# Motor_Temp_Measurement.net
KiCad netlist of a schematic drawn in Altium Designer
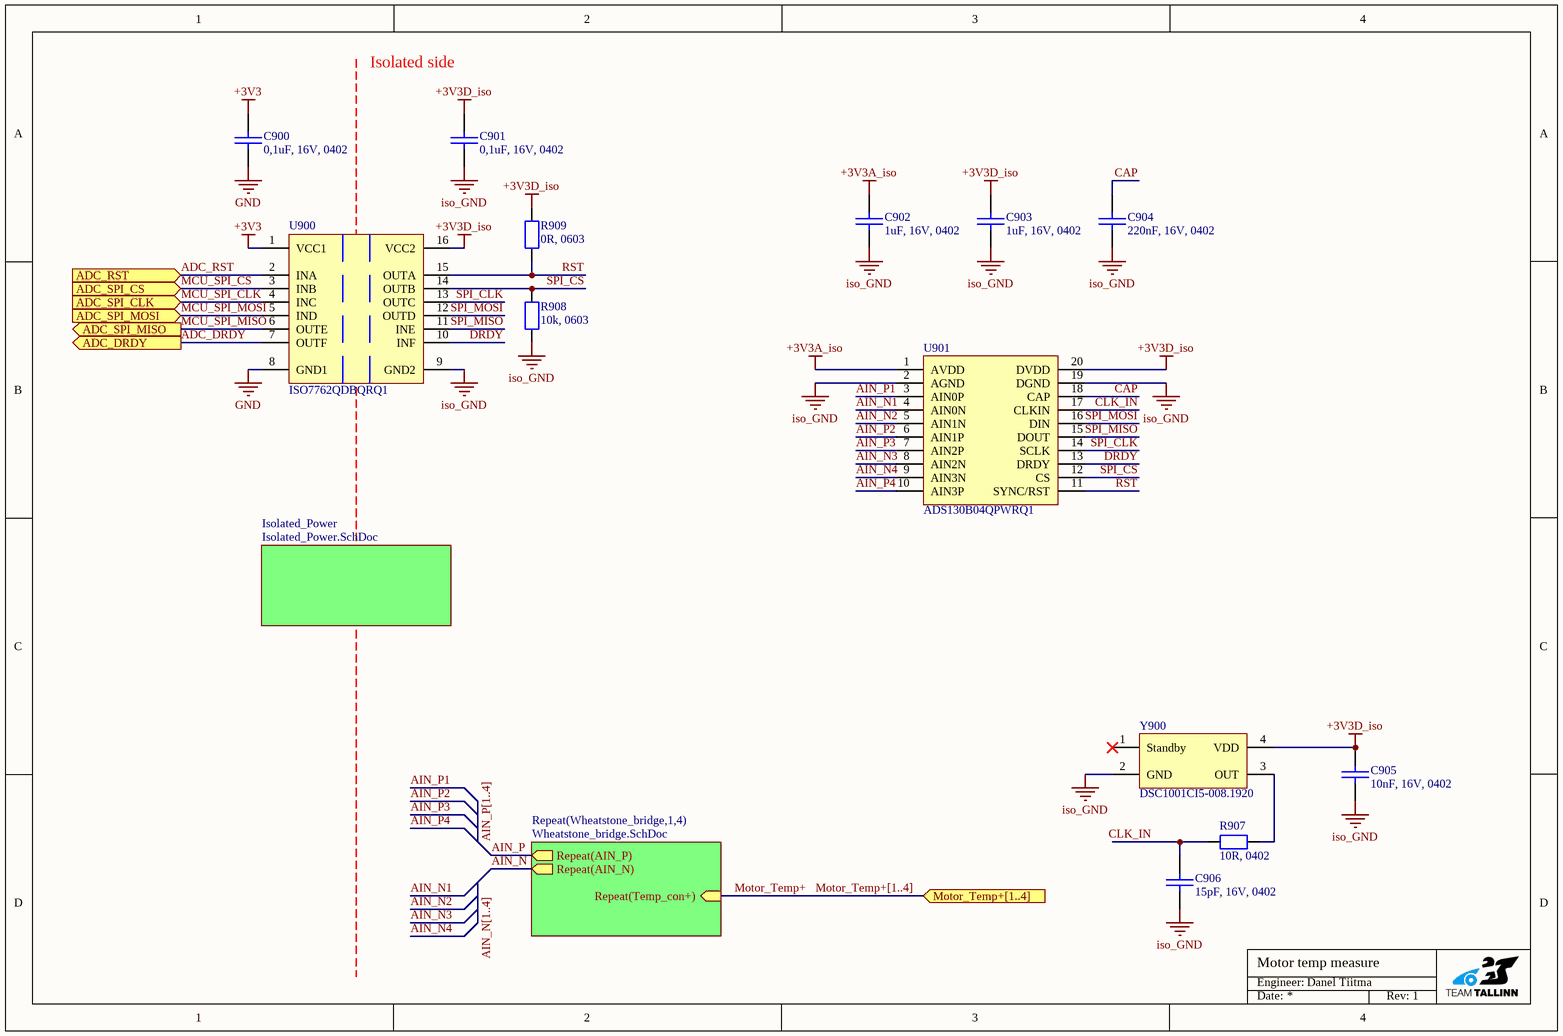
[diagram p0: Motor_Temp_Measurement.SchDoc]

(export (version "E")
  (design (tool "Eeschema 10.0.6"))
  (components
    (comp (ref "C900")
      (value "0,1uF, 16V, 0402")
      (footprint "CAP [0402] 1005")
      (description "Default capacitor part")
      (libsource (lib "Formula Student Team Tallinn (Estonia)") (part "Capacitor"))
    )
    (comp (ref "C901")
      (value "0,1uF, 16V, 0402")
      (footprint "CAP [0402] 1005")
      (description "Default capacitor part")
      (libsource (lib "Formula Student Team Tallinn (Estonia)") (part "Capacitor"))
    )
    (comp (ref "C902")
      (value "1uF, 16V, 0402")
      (footprint "CAP [0402] 1005")
      (description "Default capacitor part")
      (libsource (lib "Formula Student Team Tallinn (Estonia)") (part "Capacitor"))
    )
    (comp (ref "C903")
      (value "1uF, 16V, 0402")
      (footprint "CAP [0402] 1005")
      (description "Default capacitor part")
      (libsource (lib "Formula Student Team Tallinn (Estonia)") (part "Capacitor"))
    )
    (comp (ref "C904")
      (value "220nF, 16V, 0402")
      (footprint "CAP [0402] 1005")
      (description "Default capacitor part")
      (libsource (lib "Formula Student Team Tallinn (Estonia)") (part "Capacitor"))
    )
    (comp (ref "C905")
      (value "10nF, 16V, 0402")
      (footprint "CAP [0402] 1005")
      (description "Default capacitor part")
      (libsource (lib "Formula Student Team Tallinn (Estonia)") (part "Capacitor"))
    )
    (comp (ref "C906")
      (value "15pF, 16V, 0402")
      (footprint "CAP [0402] 1005")
      (description "Default capacitor part")
      (libsource (lib "Formula Student Team Tallinn (Estonia)") (part "Capacitor"))
    )
    (comp (ref "R907")
      (value "10R, 0402")
      (footprint "RES [0402] 1005")
      (description "Standard resistor part")
      (libsource (lib "Formula Student Team Tallinn (Estonia)") (part "Resistor"))
    )
    (comp (ref "R908")
      (value "10k, 0603")
      (footprint "RES [0603] 1608")
      (description "Standard resistor part")
      (libsource (lib "Formula Student Team Tallinn (Estonia)") (part "Resistor"))
    )
    (comp (ref "R909")
      (value "0R, 0603")
      (footprint "RES [0603] 1608")
      (description "Standard resistor part")
      (libsource (lib "Formula Student Team Tallinn (Estonia)") (part "Resistor"))
    )
    (comp (ref "U900")
      (value "ISO7762QDBQRQ1")
      (footprint "SSOP-16")
      (description "Interface Circuit, CMOS, PDSO16")
      (fields (field (name "MANUFACTURER") "Texas Instruments"))
      (libsource (lib "Formula Student Team Tallinn (Estonia)") (part "ISO7761DBQ"))
    )
    (comp (ref "U901")
      (value "ADS130B04QPWRQ1")
      (footprint "TSSOP-20")
      (libsource (lib "Formula Student Team Tallinn (Estonia)") (part "ADS130B04QPWRQ1"))
    )
    (comp (ref "Y900")
      (value "DSC1001CI5-008.1920")
      (footprint "Crystal 3.2x2.5mm")
      (description "CMOS Output Clock Oscillator, 8.192MHz Nom")
      (fields
        (field (name "MANUFACTURER PART NUMBER") "DSC1001DI5-008.1920T")
        (field (name "MANUFACTURER") "Microchip")
      )
      (libsource (lib "Formula Student Team Tallinn (Estonia)") (part "DSC1001CI5-008.1920"))
    )
  )
  (nets
    (net (code "5") (name "+3V3") (class "Default")
      (node (ref "C900") (pin "1") (pinfunction "1_1") (pintype "passive"))
      (node (ref "U900") (pin "1") (pinfunction "VCC1_1") (pintype "passive"))
    )
    (net (code "6") (name "+3V3A_iso") (class "Default")
      (node (ref "C902") (pin "2") (pinfunction "2_2") (pintype "passive"))
      (node (ref "U901") (pin "1") (pinfunction "AVDD_1") (pintype "passive"))
    )
    (net (code "7") (name "+3V3D_iso") (class "Default")
      (node (ref "C901") (pin "2") (pinfunction "2_2") (pintype "passive"))
      (node (ref "C903") (pin "2") (pinfunction "2_2") (pintype "passive"))
      (node (ref "C905") (pin "1") (pinfunction "1_1") (pintype "passive"))
      (node (ref "R909") (pin "1") (pinfunction "1_1") (pintype "passive"))
      (node (ref "U900") (pin "16") (pinfunction "VCC2_16") (pintype "passive"))
      (node (ref "U901") (pin "20") (pinfunction "DVDD_20") (pintype "passive"))
      (node (ref "Y900") (pin "4") (pinfunction "VDD_4") (pintype "passive"))
    )
    (net (code "8") (name "/ADC_DRDY") (class "Default")
      (node (ref "U900") (pin "7") (pinfunction "OUTF_7") (pintype "passive"))
    )
    (net (code "9") (name "/ADC_RST") (class "Default")
      (node (ref "U900") (pin "2") (pinfunction "INA_2") (pintype "passive"))
    )
    (net (code "11") (name "/AIN_N1") (class "Default")
      (node (ref "U901") (pin "4") (pinfunction "AIN0N_4") (pintype "passive"))
    )
    (net (code "12") (name "/AIN_N2") (class "Default")
      (node (ref "U901") (pin "5") (pinfunction "AIN1N_5") (pintype "passive"))
    )
    (net (code "13") (name "/AIN_N3") (class "Default")
      (node (ref "U901") (pin "8") (pinfunction "AIN2N_8") (pintype "passive"))
    )
    (net (code "14") (name "/AIN_N4") (class "Default")
      (node (ref "U901") (pin "9") (pinfunction "AIN3N_9") (pintype "passive"))
    )
    (net (code "17") (name "/AIN_P1") (class "Default")
      (node (ref "U901") (pin "3") (pinfunction "AIN0P_3") (pintype "passive"))
    )
    (net (code "18") (name "/AIN_P2") (class "Default")
      (node (ref "U901") (pin "6") (pinfunction "AIN1P_6") (pintype "passive"))
    )
    (net (code "19") (name "/AIN_P3") (class "Default")
      (node (ref "U901") (pin "7") (pinfunction "AIN2P_7") (pintype "passive"))
    )
    (net (code "20") (name "/AIN_P4") (class "Default")
      (node (ref "U901") (pin "10") (pinfunction "AIN3P_10") (pintype "passive"))
    )
    (net (code "22") (name "/CAP") (class "Default")
      (node (ref "C904") (pin "2") (pinfunction "2_2") (pintype "passive"))
      (node (ref "U901") (pin "18") (pinfunction "CAP_18") (pintype "passive"))
    )
    (net (code "23") (name "/CLK_IN") (class "Default")
      (node (ref "C906") (pin "2") (pinfunction "2_2") (pintype "passive"))
      (node (ref "R907") (pin "2") (pinfunction "2_2") (pintype "passive"))
      (node (ref "U901") (pin "17") (pinfunction "CLKIN_17") (pintype "passive"))
    )
    (net (code "24") (name "/DRDY") (class "Default")
      (node (ref "U900") (pin "10") (pinfunction "INF_10") (pintype "passive"))
      (node (ref "U901") (pin "13") (pinfunction "DRDY_13") (pintype "passive"))
    )
    (net (code "25") (name "/MCU_SPI_CLK") (class "Default")
      (node (ref "U900") (pin "4") (pinfunction "INC_4") (pintype "passive"))
    )
    (net (code "26") (name "/MCU_SPI_CS") (class "Default")
      (node (ref "U900") (pin "3") (pinfunction "INB_3") (pintype "passive"))
    )
    (net (code "27") (name "/MCU_SPI_MISO") (class "Default")
      (node (ref "U900") (pin "6") (pinfunction "OUTE_6") (pintype "passive"))
    )
    (net (code "28") (name "/MCU_SPI_MOSI") (class "Default")
      (node (ref "U900") (pin "5") (pinfunction "IND_5") (pintype "passive"))
    )
    (net (code "31") (name "/RST") (class "Default")
      (node (ref "R909") (pin "2") (pinfunction "2_2") (pintype "passive"))
      (node (ref "U900") (pin "15") (pinfunction "OUTA_15") (pintype "passive"))
      (node (ref "U901") (pin "11") (pinfunction "SYNC/RST_11") (pintype "passive"))
    )
    (net (code "32") (name "/SPI_CLK") (class "Default")
      (node (ref "U900") (pin "13") (pinfunction "OUTC_13") (pintype "passive"))
      (node (ref "U901") (pin "14") (pinfunction "SCLK_14") (pintype "passive"))
    )
    (net (code "33") (name "/SPI_CS") (class "Default")
      (node (ref "R908") (pin "1") (pinfunction "1_1") (pintype "passive"))
      (node (ref "U900") (pin "14") (pinfunction "OUTB_14") (pintype "passive"))
      (node (ref "U901") (pin "12") (pinfunction "CS_12") (pintype "passive"))
    )
    (net (code "34") (name "/SPI_MISO") (class "Default")
      (node (ref "U900") (pin "11") (pinfunction "INE_11") (pintype "passive"))
      (node (ref "U901") (pin "15") (pinfunction "DOUT_15") (pintype "passive"))
    )
    (net (code "35") (name "/SPI_MOSI") (class "Default")
      (node (ref "U900") (pin "12") (pinfunction "OUTD_12") (pintype "passive"))
      (node (ref "U901") (pin "16") (pinfunction "DIN_16") (pintype "passive"))
    )
    (net (code "36") (name "GND") (class "Default")
      (node (ref "C900") (pin "2") (pinfunction "2_2") (pintype "passive"))
      (node (ref "U900") (pin "8") (pinfunction "GND1_8") (pintype "passive"))
    )
    (net (code "37") (name "Net-(Y900-OUT)") (class "Default")
      (node (ref "R907") (pin "1") (pinfunction "1_1") (pintype "passive"))
      (node (ref "Y900") (pin "3") (pinfunction "OUT_3") (pintype "passive"))
    )
    (net (code "38") (name "iso_GND") (class "Default")
      (node (ref "C901") (pin "1") (pinfunction "1_1") (pintype "passive"))
      (node (ref "C902") (pin "1") (pinfunction "1_1") (pintype "passive"))
      (node (ref "C903") (pin "1") (pinfunction "1_1") (pintype "passive"))
      (node (ref "C904") (pin "1") (pinfunction "1_1") (pintype "passive"))
      (node (ref "C905") (pin "2") (pinfunction "2_2") (pintype "passive"))
      (node (ref "C906") (pin "1") (pinfunction "1_1") (pintype "passive"))
      (node (ref "R908") (pin "2") (pinfunction "2_2") (pintype "passive"))
      (node (ref "U900") (pin "9") (pinfunction "GND2_9") (pintype "passive"))
      (node (ref "U901") (pin "19") (pinfunction "DGND_19") (pintype "passive"))
      (node (ref "U901") (pin "2") (pinfunction "AGND_2") (pintype "passive"))
      (node (ref "Y900") (pin "2") (pinfunction "GND_2") (pintype "passive"))
    )
    (net (code "39") (name "unconnected-(Y900-Standby-Pad1)") (class "Default")
      (node (ref "Y900") (pin "1") (pinfunction "Standby_1") (pintype "passive+no_connect"))
    )
  )
)
